# FPGA.net
KiCad netlist of a schematic drawn in Altium Designer
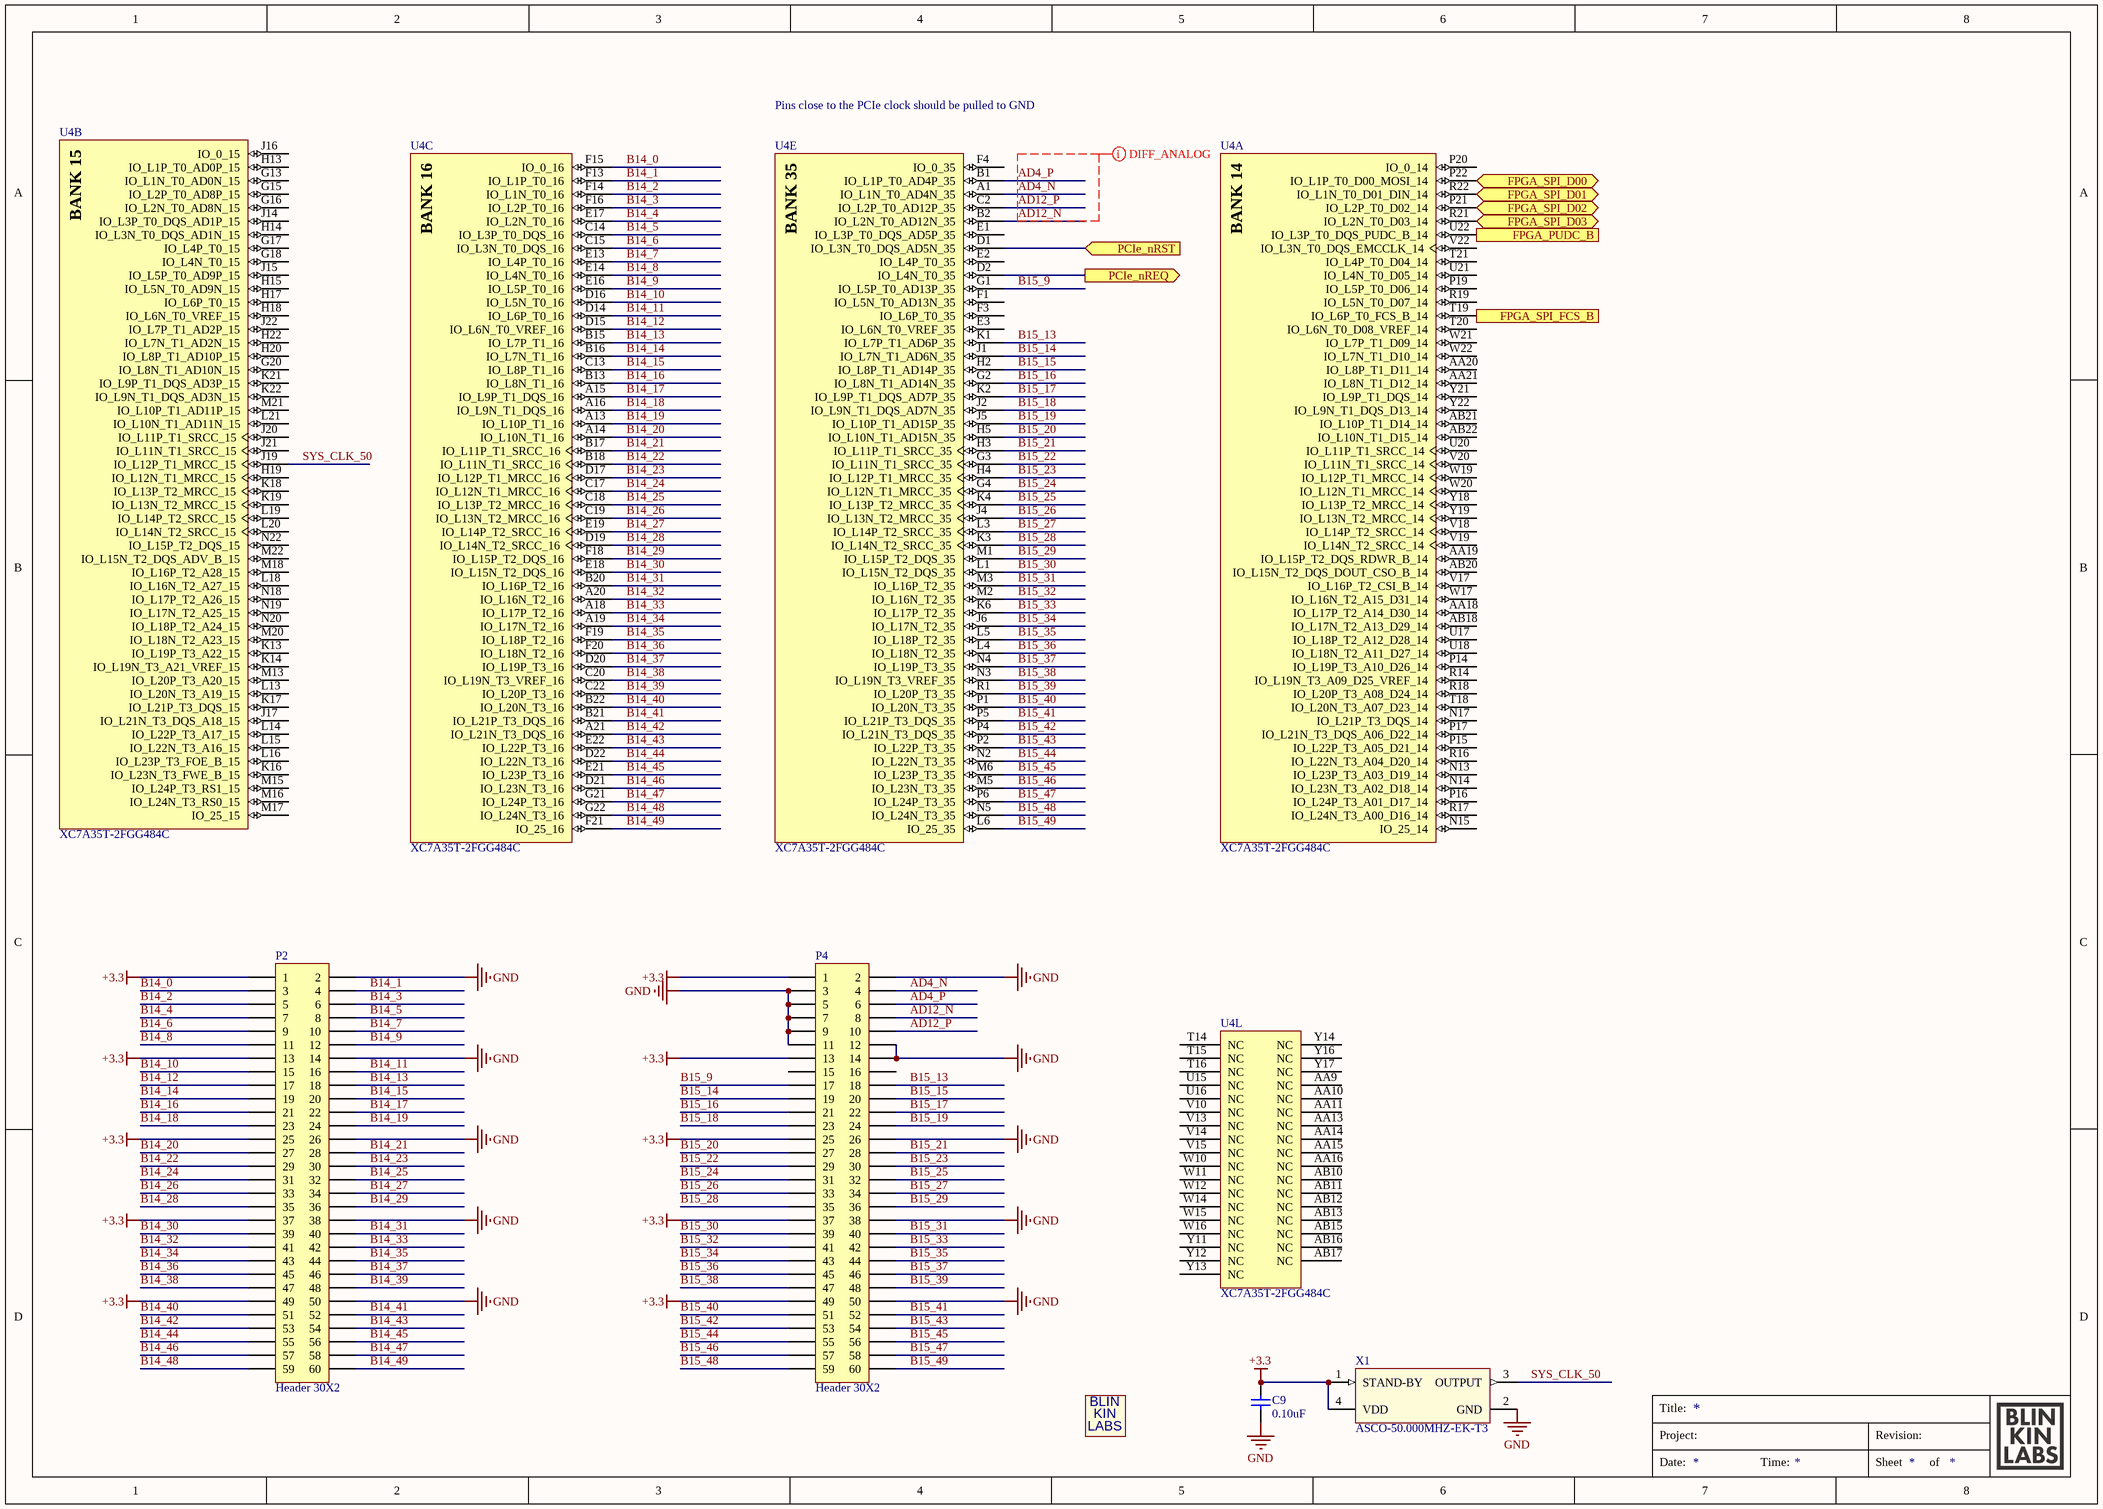
[diagram p0: FPGA.SchDoc]

(export (version "E")
  (design (tool "Eeschema 10.0.6"))
  (components
    (comp (ref "C9")
      (value "0.10uF")
      (footprint "CAPC1005X06L")
      (description "CAP CER 0.1UF 10V X5R 0402")
      (fields
        (field (name "PARTNUMBER") "GRM155R61A104KA01D")
        (field (name "DIGI-KEY PART NUMBER") "490-1318-1-ND")
      )
      (libsource (lib "cap_murata") (part "CAPACITOR"))
    )
    (comp (ref "L1")
      (value "BLINKINLABS_LOGO")
      (footprint "BLINKINLABS_LOGO")
      (description "Square logo")
      (libsource (lib "Blinkinlabs") (part "BLINKINLABS_LOGO"))
    )
    (comp (ref "P2")
      (value "Header 30X2")
      (footprint "HDR2X30")
      (description "Header, 30-Pin, Dual row")
      (fields (field (name "PUBLISHER") "Altium Limited"))
      (libsource (lib "Miscellaneous Connectors") (part "Header 30X2"))
    )
    (comp (ref "P4")
      (value "Header 30X2")
      (footprint "HDR2X30")
      (description "Header, 30-Pin, Dual row")
      (fields (field (name "PUBLISHER") "Altium Limited"))
      (libsource (lib "Miscellaneous Connectors") (part "Header 30X2"))
    )
    (comp (ref "U4")
      (value "XC7A35T-2FGG484C")
      (footprint "FGG484")
      (description "Artix-7 FPGA, 250 User I/Os, 4 GTP, 484-Ball BGA, Speed Grade 2, Commercial Grade, Pb-Free")
      (fields (field (name "MANUFACTURER") "Xilinx"))
      (libsource (lib "Altium Content Vault") (part "XLNX-XC7A35T-FGG484"))
    )
    (comp (ref "X1")
      (value "ASCO-50.000MHZ-EK-T3")
      (footprint "ABRA-ASCO-50.000MHZ-EK-T3-4_V")
      (description "Crystal Clock Oscillator, 50 MHz, -20 to 70 degC, 1.6 x 1.2 x 0.7 mm SMD")
      (fields (field (name "MANUFACTURER") "Abracon"))
      (libsource (lib "Altium Content Vault") (part "ABRA-ASCO-50_000MHZ-EK-T3-4"))
    )
  )
  (nets
    (net (code "1") (name "+3.3") (class "Default")
      (node (ref "C9") (pin "2") (pinfunction "2_2") (pintype "passive"))
      (node (ref "P2") (pin "1") (pinfunction "1_1") (pintype "passive"))
      (node (ref "P2") (pin "13") (pinfunction "13_13") (pintype "passive"))
      (node (ref "P2") (pin "25") (pinfunction "25_25") (pintype "passive"))
      (node (ref "P2") (pin "37") (pinfunction "37_37") (pintype "passive"))
      (node (ref "P2") (pin "49") (pinfunction "49_49") (pintype "passive"))
      (node (ref "P4") (pin "1") (pinfunction "1_1") (pintype "passive"))
      (node (ref "P4") (pin "13") (pinfunction "13_13") (pintype "passive"))
      (node (ref "P4") (pin "25") (pinfunction "25_25") (pintype "passive"))
      (node (ref "P4") (pin "37") (pinfunction "37_37") (pintype "passive"))
      (node (ref "P4") (pin "49") (pinfunction "49_49") (pintype "passive"))
      (node (ref "X1") (pin "1") (pinfunction "STAND-BY_1") (pintype "input"))
      (node (ref "X1") (pin "4") (pinfunction "VDD_4") (pintype "power_in"))
    )
    (net (code "2") (name "/AD4_N") (class "Default")
      (node (ref "P4") (pin "4") (pinfunction "4_4") (pintype "passive"))
      (node (ref "U4") (pin "A1") (pinfunction "IO_L1N_T0_AD4N_35_A1") (pintype "bidirectional"))
    )
    (net (code "3") (name "/AD4_P") (class "Default")
      (node (ref "P4") (pin "6") (pinfunction "6_6") (pintype "passive"))
      (node (ref "U4") (pin "B1") (pinfunction "IO_L1P_T0_AD4P_35_B1") (pintype "bidirectional"))
    )
    (net (code "4") (name "/AD12_N") (class "Default")
      (node (ref "P4") (pin "8") (pinfunction "8_8") (pintype "passive"))
      (node (ref "U4") (pin "B2") (pinfunction "IO_L2N_T0_AD12N_35_B2") (pintype "bidirectional"))
    )
    (net (code "5") (name "/AD12_P") (class "Default")
      (node (ref "P4") (pin "10") (pinfunction "10_10") (pintype "passive"))
      (node (ref "U4") (pin "C2") (pinfunction "IO_L2P_T0_AD12P_35_C2") (pintype "bidirectional"))
    )
    (net (code "6") (name "/B14_0") (class "Default")
      (node (ref "P2") (pin "3") (pinfunction "3_3") (pintype "passive"))
      (node (ref "U4") (pin "F15") (pinfunction "IO_0_16_F15") (pintype "bidirectional"))
    )
    (net (code "7") (name "/B14_1") (class "Default")
      (node (ref "P2") (pin "4") (pinfunction "4_4") (pintype "passive"))
      (node (ref "U4") (pin "F13") (pinfunction "IO_L1P_T0_16_F13") (pintype "bidirectional"))
    )
    (net (code "8") (name "/B14_2") (class "Default")
      (node (ref "P2") (pin "5") (pinfunction "5_5") (pintype "passive"))
      (node (ref "U4") (pin "F14") (pinfunction "IO_L1N_T0_16_F14") (pintype "bidirectional"))
    )
    (net (code "9") (name "/B14_3") (class "Default")
      (node (ref "P2") (pin "6") (pinfunction "6_6") (pintype "passive"))
      (node (ref "U4") (pin "F16") (pinfunction "IO_L2P_T0_16_F16") (pintype "bidirectional"))
    )
    (net (code "10") (name "/B14_4") (class "Default")
      (node (ref "P2") (pin "7") (pinfunction "7_7") (pintype "passive"))
      (node (ref "U4") (pin "E17") (pinfunction "IO_L2N_T0_16_E17") (pintype "bidirectional"))
    )
    (net (code "11") (name "/B14_5") (class "Default")
      (node (ref "P2") (pin "8") (pinfunction "8_8") (pintype "passive"))
      (node (ref "U4") (pin "C14") (pinfunction "IO_L3P_T0_DQS_16_C14") (pintype "bidirectional"))
    )
    (net (code "12") (name "/B14_6") (class "Default")
      (node (ref "P2") (pin "9") (pinfunction "9_9") (pintype "passive"))
      (node (ref "U4") (pin "C15") (pinfunction "IO_L3N_T0_DQS_16_C15") (pintype "bidirectional"))
    )
    (net (code "13") (name "/B14_7") (class "Default")
      (node (ref "P2") (pin "10") (pinfunction "10_10") (pintype "passive"))
      (node (ref "U4") (pin "E13") (pinfunction "IO_L4P_T0_16_E13") (pintype "bidirectional"))
    )
    (net (code "14") (name "/B14_8") (class "Default")
      (node (ref "P2") (pin "11") (pinfunction "11_11") (pintype "passive"))
      (node (ref "U4") (pin "E14") (pinfunction "IO_L4N_T0_16_E14") (pintype "bidirectional"))
    )
    (net (code "15") (name "/B14_9") (class "Default")
      (node (ref "P2") (pin "12") (pinfunction "12_12") (pintype "passive"))
      (node (ref "U4") (pin "E16") (pinfunction "IO_L5P_T0_16_E16") (pintype "bidirectional"))
    )
    (net (code "16") (name "/B14_10") (class "Default")
      (node (ref "P2") (pin "15") (pinfunction "15_15") (pintype "passive"))
      (node (ref "U4") (pin "D16") (pinfunction "IO_L5N_T0_16_D16") (pintype "bidirectional"))
    )
    (net (code "17") (name "/B14_11") (class "Default")
      (node (ref "P2") (pin "16") (pinfunction "16_16") (pintype "passive"))
      (node (ref "U4") (pin "D14") (pinfunction "IO_L6P_T0_16_D14") (pintype "bidirectional"))
    )
    (net (code "18") (name "/B14_12") (class "Default")
      (node (ref "P2") (pin "17") (pinfunction "17_17") (pintype "passive"))
      (node (ref "U4") (pin "D15") (pinfunction "IO_L6N_T0_VREF_16_D15") (pintype "bidirectional"))
    )
    (net (code "19") (name "/B14_13") (class "Default")
      (node (ref "P2") (pin "18") (pinfunction "18_18") (pintype "passive"))
      (node (ref "U4") (pin "B15") (pinfunction "IO_L7P_T1_16_B15") (pintype "bidirectional"))
    )
    (net (code "20") (name "/B14_14") (class "Default")
      (node (ref "P2") (pin "19") (pinfunction "19_19") (pintype "passive"))
      (node (ref "U4") (pin "B16") (pinfunction "IO_L7N_T1_16_B16") (pintype "bidirectional"))
    )
    (net (code "21") (name "/B14_15") (class "Default")
      (node (ref "P2") (pin "20") (pinfunction "20_20") (pintype "passive"))
      (node (ref "U4") (pin "C13") (pinfunction "IO_L8P_T1_16_C13") (pintype "bidirectional"))
    )
    (net (code "22") (name "/B14_16") (class "Default")
      (node (ref "P2") (pin "21") (pinfunction "21_21") (pintype "passive"))
      (node (ref "U4") (pin "B13") (pinfunction "IO_L8N_T1_16_B13") (pintype "bidirectional"))
    )
    (net (code "23") (name "/B14_17") (class "Default")
      (node (ref "P2") (pin "22") (pinfunction "22_22") (pintype "passive"))
      (node (ref "U4") (pin "A15") (pinfunction "IO_L9P_T1_DQS_16_A15") (pintype "bidirectional"))
    )
    (net (code "24") (name "/B14_18") (class "Default")
      (node (ref "P2") (pin "23") (pinfunction "23_23") (pintype "passive"))
      (node (ref "U4") (pin "A16") (pinfunction "IO_L9N_T1_DQS_16_A16") (pintype "bidirectional"))
    )
    (net (code "25") (name "/B14_19") (class "Default")
      (node (ref "P2") (pin "24") (pinfunction "24_24") (pintype "passive"))
      (node (ref "U4") (pin "A13") (pinfunction "IO_L10P_T1_16_A13") (pintype "bidirectional"))
    )
    (net (code "26") (name "/B14_20") (class "Default")
      (node (ref "P2") (pin "27") (pinfunction "27_27") (pintype "passive"))
      (node (ref "U4") (pin "A14") (pinfunction "IO_L10N_T1_16_A14") (pintype "bidirectional"))
    )
    (net (code "27") (name "/B14_21") (class "Default")
      (node (ref "P2") (pin "28") (pinfunction "28_28") (pintype "passive"))
      (node (ref "U4") (pin "B17") (pinfunction "IO_L11P_T1_SRCC_16_B17") (pintype "bidirectional"))
    )
    (net (code "28") (name "/B14_22") (class "Default")
      (node (ref "P2") (pin "29") (pinfunction "29_29") (pintype "passive"))
      (node (ref "U4") (pin "B18") (pinfunction "IO_L11N_T1_SRCC_16_B18") (pintype "bidirectional"))
    )
    (net (code "29") (name "/B14_23") (class "Default")
      (node (ref "P2") (pin "30") (pinfunction "30_30") (pintype "passive"))
      (node (ref "U4") (pin "D17") (pinfunction "IO_L12P_T1_MRCC_16_D17") (pintype "bidirectional"))
    )
    (net (code "30") (name "/B14_24") (class "Default")
      (node (ref "P2") (pin "31") (pinfunction "31_31") (pintype "passive"))
      (node (ref "U4") (pin "C17") (pinfunction "IO_L12N_T1_MRCC_16_C17") (pintype "bidirectional"))
    )
    (net (code "31") (name "/B14_25") (class "Default")
      (node (ref "P2") (pin "32") (pinfunction "32_32") (pintype "passive"))
      (node (ref "U4") (pin "C18") (pinfunction "IO_L13P_T2_MRCC_16_C18") (pintype "bidirectional"))
    )
    (net (code "32") (name "/B14_26") (class "Default")
      (node (ref "P2") (pin "33") (pinfunction "33_33") (pintype "passive"))
      (node (ref "U4") (pin "C19") (pinfunction "IO_L13N_T2_MRCC_16_C19") (pintype "bidirectional"))
    )
    (net (code "33") (name "/B14_27") (class "Default")
      (node (ref "P2") (pin "34") (pinfunction "34_34") (pintype "passive"))
      (node (ref "U4") (pin "E19") (pinfunction "IO_L14P_T2_SRCC_16_E19") (pintype "bidirectional"))
    )
    (net (code "34") (name "/B14_28") (class "Default")
      (node (ref "P2") (pin "35") (pinfunction "35_35") (pintype "passive"))
      (node (ref "U4") (pin "D19") (pinfunction "IO_L14N_T2_SRCC_16_D19") (pintype "bidirectional"))
    )
    (net (code "35") (name "/B14_29") (class "Default")
      (node (ref "P2") (pin "36") (pinfunction "36_36") (pintype "passive"))
      (node (ref "U4") (pin "F18") (pinfunction "IO_L15P_T2_DQS_16_F18") (pintype "bidirectional"))
    )
    (net (code "36") (name "/B14_30") (class "Default")
      (node (ref "P2") (pin "39") (pinfunction "39_39") (pintype "passive"))
      (node (ref "U4") (pin "E18") (pinfunction "IO_L15N_T2_DQS_16_E18") (pintype "bidirectional"))
    )
    (net (code "37") (name "/B14_31") (class "Default")
      (node (ref "P2") (pin "40") (pinfunction "40_40") (pintype "passive"))
      (node (ref "U4") (pin "B20") (pinfunction "IO_L16P_T2_16_B20") (pintype "bidirectional"))
    )
    (net (code "38") (name "/B14_32") (class "Default")
      (node (ref "P2") (pin "41") (pinfunction "41_41") (pintype "passive"))
      (node (ref "U4") (pin "A20") (pinfunction "IO_L16N_T2_16_A20") (pintype "bidirectional"))
    )
    (net (code "39") (name "/B14_33") (class "Default")
      (node (ref "P2") (pin "42") (pinfunction "42_42") (pintype "passive"))
      (node (ref "U4") (pin "A18") (pinfunction "IO_L17P_T2_16_A18") (pintype "bidirectional"))
    )
    (net (code "40") (name "/B14_34") (class "Default")
      (node (ref "P2") (pin "43") (pinfunction "43_43") (pintype "passive"))
      (node (ref "U4") (pin "A19") (pinfunction "IO_L17N_T2_16_A19") (pintype "bidirectional"))
    )
    (net (code "41") (name "/B14_35") (class "Default")
      (node (ref "P2") (pin "44") (pinfunction "44_44") (pintype "passive"))
      (node (ref "U4") (pin "F19") (pinfunction "IO_L18P_T2_16_F19") (pintype "bidirectional"))
    )
    (net (code "42") (name "/B14_36") (class "Default")
      (node (ref "P2") (pin "45") (pinfunction "45_45") (pintype "passive"))
      (node (ref "U4") (pin "F20") (pinfunction "IO_L18N_T2_16_F20") (pintype "bidirectional"))
    )
    (net (code "43") (name "/B14_37") (class "Default")
      (node (ref "P2") (pin "46") (pinfunction "46_46") (pintype "passive"))
      (node (ref "U4") (pin "D20") (pinfunction "IO_L19P_T3_16_D20") (pintype "bidirectional"))
    )
    (net (code "44") (name "/B14_38") (class "Default")
      (node (ref "P2") (pin "47") (pinfunction "47_47") (pintype "passive"))
      (node (ref "U4") (pin "C20") (pinfunction "IO_L19N_T3_VREF_16_C20") (pintype "bidirectional"))
    )
    (net (code "45") (name "/B14_39") (class "Default")
      (node (ref "P2") (pin "48") (pinfunction "48_48") (pintype "passive"))
      (node (ref "U4") (pin "C22") (pinfunction "IO_L20P_T3_16_C22") (pintype "bidirectional"))
    )
    (net (code "46") (name "/B14_40") (class "Default")
      (node (ref "P2") (pin "51") (pinfunction "51_51") (pintype "passive"))
      (node (ref "U4") (pin "B22") (pinfunction "IO_L20N_T3_16_B22") (pintype "bidirectional"))
    )
    (net (code "47") (name "/B14_41") (class "Default")
      (node (ref "P2") (pin "52") (pinfunction "52_52") (pintype "passive"))
      (node (ref "U4") (pin "B21") (pinfunction "IO_L21P_T3_DQS_16_B21") (pintype "bidirectional"))
    )
    (net (code "48") (name "/B14_42") (class "Default")
      (node (ref "P2") (pin "53") (pinfunction "53_53") (pintype "passive"))
      (node (ref "U4") (pin "A21") (pinfunction "IO_L21N_T3_DQS_16_A21") (pintype "bidirectional"))
    )
    (net (code "49") (name "/B14_43") (class "Default")
      (node (ref "P2") (pin "54") (pinfunction "54_54") (pintype "passive"))
      (node (ref "U4") (pin "E22") (pinfunction "IO_L22P_T3_16_E22") (pintype "bidirectional"))
    )
    (net (code "50") (name "/B14_44") (class "Default")
      (node (ref "P2") (pin "55") (pinfunction "55_55") (pintype "passive"))
      (node (ref "U4") (pin "D22") (pinfunction "IO_L22N_T3_16_D22") (pintype "bidirectional"))
    )
    (net (code "51") (name "/B14_45") (class "Default")
      (node (ref "P2") (pin "56") (pinfunction "56_56") (pintype "passive"))
      (node (ref "U4") (pin "E21") (pinfunction "IO_L23P_T3_16_E21") (pintype "bidirectional"))
    )
    (net (code "52") (name "/B14_46") (class "Default")
      (node (ref "P2") (pin "57") (pinfunction "57_57") (pintype "passive"))
      (node (ref "U4") (pin "D21") (pinfunction "IO_L23N_T3_16_D21") (pintype "bidirectional"))
    )
    (net (code "53") (name "/B14_47") (class "Default")
      (node (ref "P2") (pin "58") (pinfunction "58_58") (pintype "passive"))
      (node (ref "U4") (pin "G21") (pinfunction "IO_L24P_T3_16_G21") (pintype "bidirectional"))
    )
    (net (code "54") (name "/B14_48") (class "Default")
      (node (ref "P2") (pin "59") (pinfunction "59_59") (pintype "passive"))
      (node (ref "U4") (pin "G22") (pinfunction "IO_L24N_T3_16_G22") (pintype "bidirectional"))
    )
    (net (code "55") (name "/B14_49") (class "Default")
      (node (ref "P2") (pin "60") (pinfunction "60_60") (pintype "passive"))
      (node (ref "U4") (pin "F21") (pinfunction "IO_25_16_F21") (pintype "bidirectional"))
    )
    (net (code "56") (name "/B15_9") (class "Default")
      (node (ref "P4") (pin "17") (pinfunction "17_17") (pintype "passive"))
      (node (ref "U4") (pin "G1") (pinfunction "IO_L5P_T0_AD13P_35_G1") (pintype "bidirectional"))
    )
    (net (code "57") (name "/B15_13") (class "Default")
      (node (ref "P4") (pin "18") (pinfunction "18_18") (pintype "passive"))
      (node (ref "U4") (pin "K1") (pinfunction "IO_L7P_T1_AD6P_35_K1") (pintype "bidirectional"))
    )
    (net (code "58") (name "/B15_14") (class "Default")
      (node (ref "P4") (pin "19") (pinfunction "19_19") (pintype "passive"))
      (node (ref "U4") (pin "J1") (pinfunction "IO_L7N_T1_AD6N_35_J1") (pintype "bidirectional"))
    )
    (net (code "59") (name "/B15_15") (class "Default")
      (node (ref "P4") (pin "20") (pinfunction "20_20") (pintype "passive"))
      (node (ref "U4") (pin "H2") (pinfunction "IO_L8P_T1_AD14P_35_H2") (pintype "bidirectional"))
    )
    (net (code "60") (name "/B15_16") (class "Default")
      (node (ref "P4") (pin "21") (pinfunction "21_21") (pintype "passive"))
      (node (ref "U4") (pin "G2") (pinfunction "IO_L8N_T1_AD14N_35_G2") (pintype "bidirectional"))
    )
    (net (code "61") (name "/B15_17") (class "Default")
      (node (ref "P4") (pin "22") (pinfunction "22_22") (pintype "passive"))
      (node (ref "U4") (pin "K2") (pinfunction "IO_L9P_T1_DQS_AD7P_35_K2") (pintype "bidirectional"))
    )
    (net (code "62") (name "/B15_18") (class "Default")
      (node (ref "P4") (pin "23") (pinfunction "23_23") (pintype "passive"))
      (node (ref "U4") (pin "J2") (pinfunction "IO_L9N_T1_DQS_AD7N_35_J2") (pintype "bidirectional"))
    )
    (net (code "63") (name "/B15_19") (class "Default")
      (node (ref "P4") (pin "24") (pinfunction "24_24") (pintype "passive"))
      (node (ref "U4") (pin "J5") (pinfunction "IO_L10P_T1_AD15P_35_J5") (pintype "bidirectional"))
    )
    (net (code "64") (name "/B15_20") (class "Default")
      (node (ref "P4") (pin "27") (pinfunction "27_27") (pintype "passive"))
      (node (ref "U4") (pin "H5") (pinfunction "IO_L10N_T1_AD15N_35_H5") (pintype "bidirectional"))
    )
    (net (code "65") (name "/B15_21") (class "Default")
      (node (ref "P4") (pin "28") (pinfunction "28_28") (pintype "passive"))
      (node (ref "U4") (pin "H3") (pinfunction "IO_L11P_T1_SRCC_35_H3") (pintype "bidirectional"))
    )
    (net (code "66") (name "/B15_22") (class "Default")
      (node (ref "P4") (pin "29") (pinfunction "29_29") (pintype "passive"))
      (node (ref "U4") (pin "G3") (pinfunction "IO_L11N_T1_SRCC_35_G3") (pintype "bidirectional"))
    )
    (net (code "67") (name "/B15_23") (class "Default")
      (node (ref "P4") (pin "30") (pinfunction "30_30") (pintype "passive"))
      (node (ref "U4") (pin "H4") (pinfunction "IO_L12P_T1_MRCC_35_H4") (pintype "bidirectional"))
    )
    (net (code "68") (name "/B15_24") (class "Default")
      (node (ref "P4") (pin "31") (pinfunction "31_31") (pintype "passive"))
      (node (ref "U4") (pin "G4") (pinfunction "IO_L12N_T1_MRCC_35_G4") (pintype "bidirectional"))
    )
    (net (code "69") (name "/B15_25") (class "Default")
      (node (ref "P4") (pin "32") (pinfunction "32_32") (pintype "passive"))
      (node (ref "U4") (pin "K4") (pinfunction "IO_L13P_T2_MRCC_35_K4") (pintype "bidirectional"))
    )
    (net (code "70") (name "/B15_26") (class "Default")
      (node (ref "P4") (pin "33") (pinfunction "33_33") (pintype "passive"))
      (node (ref "U4") (pin "J4") (pinfunction "IO_L13N_T2_MRCC_35_J4") (pintype "bidirectional"))
    )
    (net (code "71") (name "/B15_27") (class "Default")
      (node (ref "P4") (pin "34") (pinfunction "34_34") (pintype "passive"))
      (node (ref "U4") (pin "L3") (pinfunction "IO_L14P_T2_SRCC_35_L3") (pintype "bidirectional"))
    )
    (net (code "72") (name "/B15_28") (class "Default")
      (node (ref "P4") (pin "35") (pinfunction "35_35") (pintype "passive"))
      (node (ref "U4") (pin "K3") (pinfunction "IO_L14N_T2_SRCC_35_K3") (pintype "bidirectional"))
    )
    (net (code "73") (name "/B15_29") (class "Default")
      (node (ref "P4") (pin "36") (pinfunction "36_36") (pintype "passive"))
      (node (ref "U4") (pin "M1") (pinfunction "IO_L15P_T2_DQS_35_M1") (pintype "bidirectional"))
    )
    (net (code "74") (name "/B15_30") (class "Default")
      (node (ref "P4") (pin "39") (pinfunction "39_39") (pintype "passive"))
      (node (ref "U4") (pin "L1") (pinfunction "IO_L15N_T2_DQS_35_L1") (pintype "bidirectional"))
    )
    (net (code "75") (name "/B15_31") (class "Default")
      (node (ref "P4") (pin "40") (pinfunction "40_40") (pintype "passive"))
      (node (ref "U4") (pin "M3") (pinfunction "IO_L16P_T2_35_M3") (pintype "bidirectional"))
    )
    (net (code "76") (name "/B15_32") (class "Default")
      (node (ref "P4") (pin "41") (pinfunction "41_41") (pintype "passive"))
      (node (ref "U4") (pin "M2") (pinfunction "IO_L16N_T2_35_M2") (pintype "bidirectional"))
    )
    (net (code "77") (name "/B15_33") (class "Default")
      (node (ref "P4") (pin "42") (pinfunction "42_42") (pintype "passive"))
      (node (ref "U4") (pin "K6") (pinfunction "IO_L17P_T2_35_K6") (pintype "bidirectional"))
    )
    (net (code "78") (name "/B15_34") (class "Default")
      (node (ref "P4") (pin "43") (pinfunction "43_43") (pintype "passive"))
      (node (ref "U4") (pin "J6") (pinfunction "IO_L17N_T2_35_J6") (pintype "bidirectional"))
    )
    (net (code "79") (name "/B15_35") (class "Default")
      (node (ref "P4") (pin "44") (pinfunction "44_44") (pintype "passive"))
      (node (ref "U4") (pin "L5") (pinfunction "IO_L18P_T2_35_L5") (pintype "bidirectional"))
    )
    (net (code "80") (name "/B15_36") (class "Default")
      (node (ref "P4") (pin "45") (pinfunction "45_45") (pintype "passive"))
      (node (ref "U4") (pin "L4") (pinfunction "IO_L18N_T2_35_L4") (pintype "bidirectional"))
    )
    (net (code "81") (name "/B15_37") (class "Default")
      (node (ref "P4") (pin "46") (pinfunction "46_46") (pintype "passive"))
      (node (ref "U4") (pin "N4") (pinfunction "IO_L19P_T3_35_N4") (pintype "bidirectional"))
    )
    (net (code "82") (name "/B15_38") (class "Default")
      (node (ref "P4") (pin "47") (pinfunction "47_47") (pintype "passive"))
      (node (ref "U4") (pin "N3") (pinfunction "IO_L19N_T3_VREF_35_N3") (pintype "bidirectional"))
    )
    (net (code "83") (name "/B15_39") (class "Default")
      (node (ref "P4") (pin "48") (pinfunction "48_48") (pintype "passive"))
      (node (ref "U4") (pin "R1") (pinfunction "IO_L20P_T3_35_R1") (pintype "bidirectional"))
    )
    (net (code "84") (name "/B15_40") (class "Default")
      (node (ref "P4") (pin "51") (pinfunction "51_51") (pintype "passive"))
      (node (ref "U4") (pin "P1") (pinfunction "IO_L20N_T3_35_P1") (pintype "bidirectional"))
    )
    (net (code "85") (name "/B15_41") (class "Default")
      (node (ref "P4") (pin "52") (pinfunction "52_52") (pintype "passive"))
      (node (ref "U4") (pin "P5") (pinfunction "IO_L21P_T3_DQS_35_P5") (pintype "bidirectional"))
    )
    (net (code "86") (name "/B15_42") (class "Default")
      (node (ref "P4") (pin "53") (pinfunction "53_53") (pintype "passive"))
      (node (ref "U4") (pin "P4") (pinfunction "IO_L21N_T3_DQS_35_P4") (pintype "bidirectional"))
    )
    (net (code "87") (name "/B15_43") (class "Default")
      (node (ref "P4") (pin "54") (pinfunction "54_54") (pintype "passive"))
      (node (ref "U4") (pin "P2") (pinfunction "IO_L22P_T3_35_P2") (pintype "bidirectional"))
    )
    (net (code "88") (name "/B15_44") (class "Default")
      (node (ref "P4") (pin "55") (pinfunction "55_55") (pintype "passive"))
      (node (ref "U4") (pin "N2") (pinfunction "IO_L22N_T3_35_N2") (pintype "bidirectional"))
    )
    (net (code "89") (name "/B15_45") (class "Default")
      (node (ref "P4") (pin "56") (pinfunction "56_56") (pintype "passive"))
      (node (ref "U4") (pin "M6") (pinfunction "IO_L23P_T3_35_M6") (pintype "bidirectional"))
    )
    (net (code "90") (name "/B15_46") (class "Default")
      (node (ref "P4") (pin "57") (pinfunction "57_57") (pintype "passive"))
      (node (ref "U4") (pin "M5") (pinfunction "IO_L23N_T3_35_M5") (pintype "bidirectional"))
    )
    (net (code "91") (name "/B15_47") (class "Default")
      (node (ref "P4") (pin "58") (pinfunction "58_58") (pintype "passive"))
      (node (ref "U4") (pin "P6") (pinfunction "IO_L24P_T3_35_P6") (pintype "bidirectional"))
    )
    (net (code "92") (name "/B15_48") (class "Default")
      (node (ref "P4") (pin "59") (pinfunction "59_59") (pintype "passive"))
      (node (ref "U4") (pin "N5") (pinfunction "IO_L24N_T3_35_N5") (pintype "bidirectional"))
    )
    (net (code "93") (name "/B15_49") (class "Default")
      (node (ref "P4") (pin "60") (pinfunction "60_60") (pintype "passive"))
      (node (ref "U4") (pin "L6") (pinfunction "IO_25_35_L6") (pintype "bidirectional"))
    )
    (net (code "94") (name "/FPGA_PUDC_B") (class "Default")
      (node (ref "U4") (pin "U22") (pinfunction "IO_L3P_T0_DQS_PUDC_B_14_U22") (pintype "bidirectional"))
    )
    (net (code "95") (name "/FPGA_SPI_D00") (class "Default")
      (node (ref "U4") (pin "P22") (pinfunction "IO_L1P_T0_D00_MOSI_14_P22") (pintype "bidirectional"))
    )
    (net (code "96") (name "/FPGA_SPI_D01") (class "Default")
      (node (ref "U4") (pin "R22") (pinfunction "IO_L1N_T0_D01_DIN_14_R22") (pintype "bidirectional"))
    )
    (net (code "97") (name "/FPGA_SPI_D02") (class "Default")
      (node (ref "U4") (pin "P21") (pinfunction "IO_L2P_T0_D02_14_P21") (pintype "bidirectional"))
    )
    (net (code "98") (name "/FPGA_SPI_D03") (class "Default")
      (node (ref "U4") (pin "R21") (pinfunction "IO_L2N_T0_D03_14_R21") (pintype "bidirectional"))
    )
    (net (code "99") (name "/FPGA_SPI_FCS_B") (class "Default")
      (node (ref "U4") (pin "T19") (pinfunction "IO_L6P_T0_FCS_B_14_T19") (pintype "bidirectional"))
    )
    (net (code "100") (name "/PCIe_nREQ") (class "Default")
      (node (ref "U4") (pin "D2") (pinfunction "IO_L4N_T0_35_D2") (pintype "bidirectional"))
    )
    (net (code "101") (name "/PCIe_nRST") (class "Default")
      (node (ref "U4") (pin "D1") (pinfunction "IO_L3N_T0_DQS_AD5N_35_D1") (pintype "bidirectional"))
    )
    (net (code "102") (name "/SYS_CLK_50") (class "Default")
      (node (ref "U4") (pin "J19") (pinfunction "IO_L12P_T1_MRCC_15_J19") (pintype "bidirectional"))
      (node (ref "X1") (pin "3") (pinfunction "OUTPUT_3") (pintype "output"))
    )
    (net (code "103") (name "GND") (class "Default")
      (node (ref "C9") (pin "1") (pinfunction "1_1") (pintype "passive"))
      (node (ref "P2") (pin "14") (pinfunction "14_14") (pintype "passive"))
      (node (ref "P2") (pin "2") (pinfunction "2_2") (pintype "passive"))
      (node (ref "P2") (pin "26") (pinfunction "26_26") (pintype "passive"))
      (node (ref "P2") (pin "38") (pinfunction "38_38") (pintype "passive"))
      (node (ref "P2") (pin "50") (pinfunction "50_50") (pintype "passive"))
      (node (ref "P4") (pin "11") (pinfunction "11_11") (pintype "passive"))
      (node (ref "P4") (pin "12") (pinfunction "12_12") (pintype "passive"))
      (node (ref "P4") (pin "14") (pinfunction "14_14") (pintype "passive"))
      (node (ref "P4") (pin "2") (pinfunction "2_2") (pintype "passive"))
      (node (ref "P4") (pin "26") (pinfunction "26_26") (pintype "passive"))
      (node (ref "P4") (pin "3") (pinfunction "3_3") (pintype "passive"))
      (node (ref "P4") (pin "38") (pinfunction "38_38") (pintype "passive"))
      (node (ref "P4") (pin "5") (pinfunction "5_5") (pintype "passive"))
      (node (ref "P4") (pin "50") (pinfunction "50_50") (pintype "passive"))
      (node (ref "P4") (pin "7") (pinfunction "7_7") (pintype "passive"))
      (node (ref "P4") (pin "9") (pinfunction "9_9") (pintype "passive"))
      (node (ref "X1") (pin "2") (pinfunction "GND_2") (pintype "power_in"))
    )
    (net (code "104") (name "unconnected-(P4-Pad15)") (class "Default")
      (node (ref "P4") (pin "15") (pinfunction "15_15") (pintype "passive"))
    )
    (net (code "105") (name "unconnected-(P4-Pad16)") (class "Default")
      (node (ref "P4") (pin "16") (pinfunction "16_16") (pintype "passive"))
    )
    (net (code "106") (name "unconnected-(U4A-IO_0_14-PadP20)") (class "Default")
      (node (ref "U4") (pin "P20") (pinfunction "IO_0_14_P20") (pintype "bidirectional"))
    )
    (net (code "107") (name "unconnected-(U4A-IO_25_14-PadN15)") (class "Default")
      (node (ref "U4") (pin "N15") (pinfunction "IO_25_14_N15") (pintype "bidirectional"))
    )
    (net (code "108") (name "unconnected-(U4A-IO_L3N_T0_DQS_EMCCLK_14-PadV22)") (class "Default")
      (node (ref "U4") (pin "V22") (pinfunction "IO_L3N_T0_DQS_EMCCLK_14_V22") (pintype "bidirectional"))
    )
    (net (code "109") (name "unconnected-(U4A-IO_L4N_T0_D05_14-PadU21)") (class "Default")
      (node (ref "U4") (pin "U21") (pinfunction "IO_L4N_T0_D05_14_U21") (pintype "bidirectional"))
    )
    (net (code "110") (name "unconnected-(U4A-IO_L4P_T0_D04_14-PadT21)") (class "Default")
      (node (ref "U4") (pin "T21") (pinfunction "IO_L4P_T0_D04_14_T21") (pintype "bidirectional"))
    )
    (net (code "111") (name "unconnected-(U4A-IO_L5N_T0_D07_14-PadR19)") (class "Default")
      (node (ref "U4") (pin "R19") (pinfunction "IO_L5N_T0_D07_14_R19") (pintype "bidirectional"))
    )
    (net (code "112") (name "unconnected-(U4A-IO_L5P_T0_D06_14-PadP19)") (class "Default")
      (node (ref "U4") (pin "P19") (pinfunction "IO_L5P_T0_D06_14_P19") (pintype "bidirectional"))
    )
    (net (code "113") (name "unconnected-(U4A-IO_L6N_T0_D08_VREF_14-PadT20)") (class "Default")
      (node (ref "U4") (pin "T20") (pinfunction "IO_L6N_T0_D08_VREF_14_T20") (pintype "bidirectional"))
    )
    (net (code "114") (name "unconnected-(U4A-IO_L7N_T1_D10_14-PadW22)") (class "Default")
      (node (ref "U4") (pin "W22") (pinfunction "IO_L7N_T1_D10_14_W22") (pintype "bidirectional"))
    )
    (net (code "115") (name "unconnected-(U4A-IO_L7P_T1_D09_14-PadW21)") (class "Default")
      (node (ref "U4") (pin "W21") (pinfunction "IO_L7P_T1_D09_14_W21") (pintype "bidirectional"))
    )
    (net (code "116") (name "unconnected-(U4A-IO_L8N_T1_D12_14-PadAA21)") (class "Default")
      (node (ref "U4") (pin "AA21") (pinfunction "IO_L8N_T1_D12_14_AA21") (pintype "bidirectional"))
    )
    (net (code "117") (name "unconnected-(U4A-IO_L8P_T1_D11_14-PadAA20)") (class "Default")
      (node (ref "U4") (pin "AA20") (pinfunction "IO_L8P_T1_D11_14_AA20") (pintype "bidirectional"))
    )
    (net (code "118") (name "unconnected-(U4A-IO_L9N_T1_DQS_D13_14-PadY22)") (class "Default")
      (node (ref "U4") (pin "Y22") (pinfunction "IO_L9N_T1_DQS_D13_14_Y22") (pintype "bidirectional"))
    )
    (net (code "119") (name "unconnected-(U4A-IO_L9P_T1_DQS_14-PadY21)") (class "Default")
      (node (ref "U4") (pin "Y21") (pinfunction "IO_L9P_T1_DQS_14_Y21") (pintype "bidirectional"))
    )
    (net (code "120") (name "unconnected-(U4A-IO_L10N_T1_D15_14-PadAB22)") (class "Default")
      (node (ref "U4") (pin "AB22") (pinfunction "IO_L10N_T1_D15_14_AB22") (pintype "bidirectional"))
    )
    (net (code "121") (name "unconnected-(U4A-IO_L10P_T1_D14_14-PadAB21)") (class "Default")
      (node (ref "U4") (pin "AB21") (pinfunction "IO_L10P_T1_D14_14_AB21") (pintype "bidirectional"))
    )
    (net (code "122") (name "unconnected-(U4A-IO_L11N_T1_SRCC_14-PadV20)") (class "Default")
      (node (ref "U4") (pin "V20") (pinfunction "IO_L11N_T1_SRCC_14_V20") (pintype "bidirectional"))
    )
    (net (code "123") (name "unconnected-(U4A-IO_L11P_T1_SRCC_14-PadU20)") (class "Default")
      (node (ref "U4") (pin "U20") (pinfunction "IO_L11P_T1_SRCC_14_U20") (pintype "bidirectional"))
    )
    (net (code "124") (name "unconnected-(U4A-IO_L12N_T1_MRCC_14-PadW20)") (class "Default")
      (node (ref "U4") (pin "W20") (pinfunction "IO_L12N_T1_MRCC_14_W20") (pintype "bidirectional"))
    )
    (net (code "125") (name "unconnected-(U4A-IO_L12P_T1_MRCC_14-PadW19)") (class "Default")
      (node (ref "U4") (pin "W19") (pinfunction "IO_L12P_T1_MRCC_14_W19") (pintype "bidirectional"))
    )
    (net (code "126") (name "unconnected-(U4A-IO_L13N_T2_MRCC_14-PadY19)") (class "Default")
      (node (ref "U4") (pin "Y19") (pinfunction "IO_L13N_T2_MRCC_14_Y19") (pintype "bidirectional"))
    )
    (net (code "127") (name "unconnected-(U4A-IO_L13P_T2_MRCC_14-PadY18)") (class "Default")
      (node (ref "U4") (pin "Y18") (pinfunction "IO_L13P_T2_MRCC_14_Y18") (pintype "bidirectional"))
    )
    (net (code "128") (name "unconnected-(U4A-IO_L14N_T2_SRCC_14-PadV19)") (class "Default")
      (node (ref "U4") (pin "V19") (pinfunction "IO_L14N_T2_SRCC_14_V19") (pintype "bidirectional"))
    )
    (net (code "129") (name "unconnected-(U4A-IO_L14P_T2_SRCC_14-PadV18)") (class "Default")
      (node (ref "U4") (pin "V18") (pinfunction "IO_L14P_T2_SRCC_14_V18") (pintype "bidirectional"))
    )
    (net (code "130") (name "unconnected-(U4A-IO_L15N_T2_DQS_DOUT_CSO_B_14-PadAB20)") (class "Default")
      (node (ref "U4") (pin "AB20") (pinfunction "IO_L15N_T2_DQS_DOUT_CSO_B_14_AB20") (pintype "bidirectional"))
    )
    (net (code "131") (name "unconnected-(U4A-IO_L15P_T2_DQS_RDWR_B_14-PadAA19)") (class "Default")
      (node (ref "U4") (pin "AA19") (pinfunction "IO_L15P_T2_DQS_RDWR_B_14_AA19") (pintype "bidirectional"))
    )
    (net (code "132") (name "unconnected-(U4A-IO_L16N_T2_A15_D31_14-PadW17)") (class "Default")
      (node (ref "U4") (pin "W17") (pinfunction "IO_L16N_T2_A15_D31_14_W17") (pintype "bidirectional"))
    )
    (net (code "133") (name "unconnected-(U4A-IO_L16P_T2_CSI_B_14-PadV17)") (class "Default")
      (node (ref "U4") (pin "V17") (pinfunction "IO_L16P_T2_CSI_B_14_V17") (pintype "bidirectional"))
    )
    (net (code "134") (name "unconnected-(U4A-IO_L17N_T2_A13_D29_14-PadAB18)") (class "Default")
      (node (ref "U4") (pin "AB18") (pinfunction "IO_L17N_T2_A13_D29_14_AB18") (pintype "bidirectional"))
    )
    (net (code "135") (name "unconnected-(U4A-IO_L17P_T2_A14_D30_14-PadAA18)") (class "Default")
      (node (ref "U4") (pin "AA18") (pinfunction "IO_L17P_T2_A14_D30_14_AA18") (pintype "bidirectional"))
    )
    (net (code "136") (name "unconnected-(U4A-IO_L18N_T2_A11_D27_14-PadU18)") (class "Default")
      (node (ref "U4") (pin "U18") (pinfunction "IO_L18N_T2_A11_D27_14_U18") (pintype "bidirectional"))
    )
    (net (code "137") (name "unconnected-(U4A-IO_L18P_T2_A12_D28_14-PadU17)") (class "Default")
      (node (ref "U4") (pin "U17") (pinfunction "IO_L18P_T2_A12_D28_14_U17") (pintype "bidirectional"))
    )
    (net (code "138") (name "unconnected-(U4A-IO_L19N_T3_A09_D25_VREF_14-PadR14)") (class "Default")
      (node (ref "U4") (pin "R14") (pinfunction "IO_L19N_T3_A09_D25_VREF_14_R14") (pintype "bidirectional"))
    )
    (net (code "139") (name "unconnected-(U4A-IO_L19P_T3_A10_D26_14-PadP14)") (class "Default")
      (node (ref "U4") (pin "P14") (pinfunction "IO_L19P_T3_A10_D26_14_P14") (pintype "bidirectional"))
    )
    (net (code "140") (name "unconnected-(U4A-IO_L20N_T3_A07_D23_14-PadT18)") (class "Default")
      (node (ref "U4") (pin "T18") (pinfunction "IO_L20N_T3_A07_D23_14_T18") (pintype "bidirectional"))
    )
    (net (code "141") (name "unconnected-(U4A-IO_L20P_T3_A08_D24_14-PadR18)") (class "Default")
      (node (ref "U4") (pin "R18") (pinfunction "IO_L20P_T3_A08_D24_14_R18") (pintype "bidirectional"))
    )
    (net (code "142") (name "unconnected-(U4A-IO_L21N_T3_DQS_A06_D22_14-PadP17)") (class "Default")
      (node (ref "U4") (pin "P17") (pinfunction "IO_L21N_T3_DQS_A06_D22_14_P17") (pintype "bidirectional"))
    )
    (net (code "143") (name "unconnected-(U4A-IO_L21P_T3_DQS_14-PadN17)") (class "Default")
      (node (ref "U4") (pin "N17") (pinfunction "IO_L21P_T3_DQS_14_N17") (pintype "bidirectional"))
    )
    (net (code "144") (name "unconnected-(U4A-IO_L22N_T3_A04_D20_14-PadR16)") (class "Default")
      (node (ref "U4") (pin "R16") (pinfunction "IO_L22N_T3_A04_D20_14_R16") (pintype "bidirectional"))
    )
    (net (code "145") (name "unconnected-(U4A-IO_L22P_T3_A05_D21_14-PadP15)") (class "Default")
      (node (ref "U4") (pin "P15") (pinfunction "IO_L22P_T3_A05_D21_14_P15") (pintype "bidirectional"))
    )
    (net (code "146") (name "unconnected-(U4A-IO_L23N_T3_A02_D18_14-PadN14)") (class "Default")
      (node (ref "U4") (pin "N14") (pinfunction "IO_L23N_T3_A02_D18_14_N14") (pintype "bidirectional"))
    )
    (net (code "147") (name "unconnected-(U4A-IO_L23P_T3_A03_D19_14-PadN13)") (class "Default")
      (node (ref "U4") (pin "N13") (pinfunction "IO_L23P_T3_A03_D19_14_N13") (pintype "bidirectional"))
    )
    (net (code "148") (name "unconnected-(U4A-IO_L24N_T3_A00_D16_14-PadR17)") (class "Default")
      (node (ref "U4") (pin "R17") (pinfunction "IO_L24N_T3_A00_D16_14_R17") (pintype "bidirectional"))
    )
    (net (code "149") (name "unconnected-(U4A-IO_L24P_T3_A01_D17_14-PadP16)") (class "Default")
      (node (ref "U4") (pin "P16") (pinfunction "IO_L24P_T3_A01_D17_14_P16") (pintype "bidirectional"))
    )
    (net (code "150") (name "unconnected-(U4B-IO_0_15-PadJ16)") (class "Default")
      (node (ref "U4") (pin "J16") (pinfunction "IO_0_15_J16") (pintype "bidirectional"))
    )
    (net (code "151") (name "unconnected-(U4B-IO_25_15-PadM17)") (class "Default")
      (node (ref "U4") (pin "M17") (pinfunction "IO_25_15_M17") (pintype "bidirectional"))
    )
    (net (code "152") (name "unconnected-(U4B-IO_L1N_T0_AD0N_15-PadG13)") (class "Default")
      (node (ref "U4") (pin "G13") (pinfunction "IO_L1N_T0_AD0N_15_G13") (pintype "bidirectional"))
    )
    (net (code "153") (name "unconnected-(U4B-IO_L1P_T0_AD0P_15-PadH13)") (class "Default")
      (node (ref "U4") (pin "H13") (pinfunction "IO_L1P_T0_AD0P_15_H13") (pintype "bidirectional"))
    )
    (net (code "154") (name "unconnected-(U4B-IO_L2N_T0_AD8N_15-PadG16)") (class "Default")
      (node (ref "U4") (pin "G16") (pinfunction "IO_L2N_T0_AD8N_15_G16") (pintype "bidirectional"))
    )
    (net (code "155") (name "unconnected-(U4B-IO_L2P_T0_AD8P_15-PadG15)") (class "Default")
      (node (ref "U4") (pin "G15") (pinfunction "IO_L2P_T0_AD8P_15_G15") (pintype "bidirectional"))
    )
    (net (code "156") (name "unconnected-(U4B-IO_L3N_T0_DQS_AD1N_15-PadH14)") (class "Default")
      (node (ref "U4") (pin "H14") (pinfunction "IO_L3N_T0_DQS_AD1N_15_H14") (pintype "bidirectional"))
    )
    (net (code "157") (name "unconnected-(U4B-IO_L3P_T0_DQS_AD1P_15-PadJ14)") (class "Default")
      (node (ref "U4") (pin "J14") (pinfunction "IO_L3P_T0_DQS_AD1P_15_J14") (pintype "bidirectional"))
    )
    (net (code "158") (name "unconnected-(U4B-IO_L4N_T0_15-PadG18)") (class "Default")
      (node (ref "U4") (pin "G18") (pinfunction "IO_L4N_T0_15_G18") (pintype "bidirectional"))
    )
    (net (code "159") (name "unconnected-(U4B-IO_L4P_T0_15-PadG17)") (class "Default")
      (node (ref "U4") (pin "G17") (pinfunction "IO_L4P_T0_15_G17") (pintype "bidirectional"))
    )
    (net (code "160") (name "unconnected-(U4B-IO_L5N_T0_AD9N_15-PadH15)") (class "Default")
      (node (ref "U4") (pin "H15") (pinfunction "IO_L5N_T0_AD9N_15_H15") (pintype "bidirectional"))
    )
    (net (code "161") (name "unconnected-(U4B-IO_L5P_T0_AD9P_15-PadJ15)") (class "Default")
      (node (ref "U4") (pin "J15") (pinfunction "IO_L5P_T0_AD9P_15_J15") (pintype "bidirectional"))
    )
    (net (code "162") (name "unconnected-(U4B-IO_L6N_T0_VREF_15-PadH18)") (class "Default")
      (node (ref "U4") (pin "H18") (pinfunction "IO_L6N_T0_VREF_15_H18") (pintype "bidirectional"))
    )
    (net (code "163") (name "unconnected-(U4B-IO_L6P_T0_15-PadH17)") (class "Default")
      (node (ref "U4") (pin "H17") (pinfunction "IO_L6P_T0_15_H17") (pintype "bidirectional"))
    )
    (net (code "164") (name "unconnected-(U4B-IO_L7N_T1_AD2N_15-PadH22)") (class "Default")
      (node (ref "U4") (pin "H22") (pinfunction "IO_L7N_T1_AD2N_15_H22") (pintype "bidirectional"))
    )
    (net (code "165") (name "unconnected-(U4B-IO_L7P_T1_AD2P_15-PadJ22)") (class "Default")
      (node (ref "U4") (pin "J22") (pinfunction "IO_L7P_T1_AD2P_15_J22") (pintype "bidirectional"))
    )
    (net (code "166") (name "unconnected-(U4B-IO_L8N_T1_AD10N_15-PadG20)") (class "Default")
      (node (ref "U4") (pin "G20") (pinfunction "IO_L8N_T1_AD10N_15_G20") (pintype "bidirectional"))
    )
    (net (code "167") (name "unconnected-(U4B-IO_L8P_T1_AD10P_15-PadH20)") (class "Default")
      (node (ref "U4") (pin "H20") (pinfunction "IO_L8P_T1_AD10P_15_H20") (pintype "bidirectional"))
    )
    (net (code "168") (name "unconnected-(U4B-IO_L9N_T1_DQS_AD3N_15-PadK22)") (class "Default")
      (node (ref "U4") (pin "K22") (pinfunction "IO_L9N_T1_DQS_AD3N_15_K22") (pintype "bidirectional"))
    )
    (net (code "169") (name "unconnected-(U4B-IO_L9P_T1_DQS_AD3P_15-PadK21)") (class "Default")
      (node (ref "U4") (pin "K21") (pinfunction "IO_L9P_T1_DQS_AD3P_15_K21") (pintype "bidirectional"))
    )
    (net (code "170") (name "unconnected-(U4B-IO_L10N_T1_AD11N_15-PadL21)") (class "Default")
      (node (ref "U4") (pin "L21") (pinfunction "IO_L10N_T1_AD11N_15_L21") (pintype "bidirectional"))
    )
    (net (code "171") (name "unconnected-(U4B-IO_L10P_T1_AD11P_15-PadM21)") (class "Default")
      (node (ref "U4") (pin "M21") (pinfunction "IO_L10P_T1_AD11P_15_M21") (pintype "bidirectional"))
    )
    (net (code "172") (name "unconnected-(U4B-IO_L11N_T1_SRCC_15-PadJ21)") (class "Default")
      (node (ref "U4") (pin "J21") (pinfunction "IO_L11N_T1_SRCC_15_J21") (pintype "bidirectional"))
    )
    (net (code "173") (name "unconnected-(U4B-IO_L11P_T1_SRCC_15-PadJ20)") (class "Default")
      (node (ref "U4") (pin "J20") (pinfunction "IO_L11P_T1_SRCC_15_J20") (pintype "bidirectional"))
    )
    (net (code "174") (name "unconnected-(U4B-IO_L12N_T1_MRCC_15-PadH19)") (class "Default")
      (node (ref "U4") (pin "H19") (pinfunction "IO_L12N_T1_MRCC_15_H19") (pintype "bidirectional"))
    )
    (net (code "175") (name "unconnected-(U4B-IO_L13N_T2_MRCC_15-PadK19)") (class "Default")
      (node (ref "U4") (pin "K19") (pinfunction "IO_L13N_T2_MRCC_15_K19") (pintype "bidirectional"))
    )
    (net (code "176") (name "unconnected-(U4B-IO_L13P_T2_MRCC_15-PadK18)") (class "Default")
      (node (ref "U4") (pin "K18") (pinfunction "IO_L13P_T2_MRCC_15_K18") (pintype "bidirectional"))
    )
    (net (code "177") (name "unconnected-(U4B-IO_L14N_T2_SRCC_15-PadL20)") (class "Default")
      (node (ref "U4") (pin "L20") (pinfunction "IO_L14N_T2_SRCC_15_L20") (pintype "bidirectional"))
    )
    (net (code "178") (name "unconnected-(U4B-IO_L14P_T2_SRCC_15-PadL19)") (class "Default")
      (node (ref "U4") (pin "L19") (pinfunction "IO_L14P_T2_SRCC_15_L19") (pintype "bidirectional"))
    )
    (net (code "179") (name "unconnected-(U4B-IO_L15N_T2_DQS_ADV_B_15-PadM22)") (class "Default")
      (node (ref "U4") (pin "M22") (pinfunction "IO_L15N_T2_DQS_ADV_B_15_M22") (pintype "bidirectional"))
    )
    (net (code "180") (name "unconnected-(U4B-IO_L15P_T2_DQS_15-PadN22)") (class "Default")
      (node (ref "U4") (pin "N22") (pinfunction "IO_L15P_T2_DQS_15_N22") (pintype "bidirectional"))
    )
    (net (code "181") (name "unconnected-(U4B-IO_L16N_T2_A27_15-PadL18)") (class "Default")
      (node (ref "U4") (pin "L18") (pinfunction "IO_L16N_T2_A27_15_L18") (pintype "bidirectional"))
    )
    (net (code "182") (name "unconnected-(U4B-IO_L16P_T2_A28_15-PadM18)") (class "Default")
      (node (ref "U4") (pin "M18") (pinfunction "IO_L16P_T2_A28_15_M18") (pintype "bidirectional"))
    )
    (net (code "183") (name "unconnected-(U4B-IO_L17N_T2_A25_15-PadN19)") (class "Default")
      (node (ref "U4") (pin "N19") (pinfunction "IO_L17N_T2_A25_15_N19") (pintype "bidirectional"))
    )
    (net (code "184") (name "unconnected-(U4B-IO_L17P_T2_A26_15-PadN18)") (class "Default")
      (node (ref "U4") (pin "N18") (pinfunction "IO_L17P_T2_A26_15_N18") (pintype "bidirectional"))
    )
    (net (code "185") (name "unconnected-(U4B-IO_L18N_T2_A23_15-PadM20)") (class "Default")
      (node (ref "U4") (pin "M20") (pinfunction "IO_L18N_T2_A23_15_M20") (pintype "bidirectional"))
    )
    (net (code "186") (name "unconnected-(U4B-IO_L18P_T2_A24_15-PadN20)") (class "Default")
      (node (ref "U4") (pin "N20") (pinfunction "IO_L18P_T2_A24_15_N20") (pintype "bidirectional"))
    )
    (net (code "187") (name "unconnected-(U4B-IO_L19N_T3_A21_VREF_15-PadK14)") (class "Default")
      (node (ref "U4") (pin "K14") (pinfunction "IO_L19N_T3_A21_VREF_15_K14") (pintype "bidirectional"))
    )
    (net (code "188") (name "unconnected-(U4B-IO_L19P_T3_A22_15-PadK13)") (class "Default")
      (node (ref "U4") (pin "K13") (pinfunction "IO_L19P_T3_A22_15_K13") (pintype "bidirectional"))
    )
    (net (code "189") (name "unconnected-(U4B-IO_L20N_T3_A19_15-PadL13)") (class "Default")
      (node (ref "U4") (pin "L13") (pinfunction "IO_L20N_T3_A19_15_L13") (pintype "bidirectional"))
    )
    (net (code "190") (name "unconnected-(U4B-IO_L20P_T3_A20_15-PadM13)") (class "Default")
      (node (ref "U4") (pin "M13") (pinfunction "IO_L20P_T3_A20_15_M13") (pintype "bidirectional"))
    )
    (net (code "191") (name "unconnected-(U4B-IO_L21N_T3_DQS_A18_15-PadJ17)") (class "Default")
      (node (ref "U4") (pin "J17") (pinfunction "IO_L21N_T3_DQS_A18_15_J17") (pintype "bidirectional"))
    )
    (net (code "192") (name "unconnected-(U4B-IO_L21P_T3_DQS_15-PadK17)") (class "Default")
      (node (ref "U4") (pin "K17") (pinfunction "IO_L21P_T3_DQS_15_K17") (pintype "bidirectional"))
    )
    (net (code "193") (name "unconnected-(U4B-IO_L22N_T3_A16_15-PadL15)") (class "Default")
      (node (ref "U4") (pin "L15") (pinfunction "IO_L22N_T3_A16_15_L15") (pintype "bidirectional"))
    )
    (net (code "194") (name "unconnected-(U4B-IO_L22P_T3_A17_15-PadL14)") (class "Default")
      (node (ref "U4") (pin "L14") (pinfunction "IO_L22P_T3_A17_15_L14") (pintype "bidirectional"))
    )
    (net (code "195") (name "unconnected-(U4B-IO_L23N_T3_FWE_B_15-PadK16)") (class "Default")
      (node (ref "U4") (pin "K16") (pinfunction "IO_L23N_T3_FWE_B_15_K16") (pintype "bidirectional"))
    )
    (net (code "196") (name "unconnected-(U4B-IO_L23P_T3_FOE_B_15-PadL16)") (class "Default")
      (node (ref "U4") (pin "L16") (pinfunction "IO_L23P_T3_FOE_B_15_L16") (pintype "bidirectional"))
    )
    (net (code "197") (name "unconnected-(U4B-IO_L24N_T3_RS0_15-PadM16)") (class "Default")
      (node (ref "U4") (pin "M16") (pinfunction "IO_L24N_T3_RS0_15_M16") (pintype "bidirectional"))
    )
    (net (code "198") (name "unconnected-(U4B-IO_L24P_T3_RS1_15-PadM15)") (class "Default")
      (node (ref "U4") (pin "M15") (pinfunction "IO_L24P_T3_RS1_15_M15") (pintype "bidirectional"))
    )
    (net (code "199") (name "unconnected-(U4E-IO_0_35-PadF4)") (class "Default")
      (node (ref "U4") (pin "F4") (pinfunction "IO_0_35_F4") (pintype "bidirectional"))
    )
    (net (code "200") (name "unconnected-(U4E-IO_L3P_T0_DQS_AD5P_35-PadE1)") (class "Default")
      (node (ref "U4") (pin "E1") (pinfunction "IO_L3P_T0_DQS_AD5P_35_E1") (pintype "bidirectional"))
    )
    (net (code "201") (name "unconnected-(U4E-IO_L4P_T0_35-PadE2)") (class "Default")
      (node (ref "U4") (pin "E2") (pinfunction "IO_L4P_T0_35_E2") (pintype "bidirectional"))
    )
    (net (code "202") (name "unconnected-(U4E-IO_L5N_T0_AD13N_35-PadF1)") (class "Default")
      (node (ref "U4") (pin "F1") (pinfunction "IO_L5N_T0_AD13N_35_F1") (pintype "bidirectional"))
    )
    (net (code "203") (name "unconnected-(U4E-IO_L6N_T0_VREF_35-PadE3)") (class "Default")
      (node (ref "U4") (pin "E3") (pinfunction "IO_L6N_T0_VREF_35_E3") (pintype "bidirectional"))
    )
    (net (code "204") (name "unconnected-(U4E-IO_L6P_T0_35-PadF3)") (class "Default")
      (node (ref "U4") (pin "F3") (pinfunction "IO_L6P_T0_35_F3") (pintype "bidirectional"))
    )
    (net (code "205") (name "unconnected-(U4L-NC-PadAA9)") (class "Default")
      (node (ref "U4") (pin "AA9") (pinfunction "NC_AA9") (pintype "passive"))
    )
    (net (code "206") (name "unconnected-(U4L-NC-PadAA10)") (class "Default")
      (node (ref "U4") (pin "AA10") (pinfunction "NC_AA10") (pintype "passive"))
    )
    (net (code "207") (name "unconnected-(U4L-NC-PadAA11)") (class "Default")
      (node (ref "U4") (pin "AA11") (pinfunction "NC_AA11") (pintype "passive"))
    )
    (net (code "208") (name "unconnected-(U4L-NC-PadAA13)") (class "Default")
      (node (ref "U4") (pin "AA13") (pinfunction "NC_AA13") (pintype "passive"))
    )
    (net (code "209") (name "unconnected-(U4L-NC-PadAA14)") (class "Default")
      (node (ref "U4") (pin "AA14") (pinfunction "NC_AA14") (pintype "passive"))
    )
    (net (code "210") (name "unconnected-(U4L-NC-PadAA15)") (class "Default")
      (node (ref "U4") (pin "AA15") (pinfunction "NC_AA15") (pintype "passive"))
    )
    (net (code "211") (name "unconnected-(U4L-NC-PadAA16)") (class "Default")
      (node (ref "U4") (pin "AA16") (pinfunction "NC_AA16") (pintype "passive"))
    )
    (net (code "212") (name "unconnected-(U4L-NC-PadAB10)") (class "Default")
      (node (ref "U4") (pin "AB10") (pinfunction "NC_AB10") (pintype "passive"))
    )
    (net (code "213") (name "unconnected-(U4L-NC-PadAB11)") (class "Default")
      (node (ref "U4") (pin "AB11") (pinfunction "NC_AB11") (pintype "passive"))
    )
    (net (code "214") (name "unconnected-(U4L-NC-PadAB12)") (class "Default")
      (node (ref "U4") (pin "AB12") (pinfunction "NC_AB12") (pintype "passive"))
    )
    (net (code "215") (name "unconnected-(U4L-NC-PadAB13)") (class "Default")
      (node (ref "U4") (pin "AB13") (pinfunction "NC_AB13") (pintype "passive"))
    )
    (net (code "216") (name "unconnected-(U4L-NC-PadAB15)") (class "Default")
      (node (ref "U4") (pin "AB15") (pinfunction "NC_AB15") (pintype "passive"))
    )
    (net (code "217") (name "unconnected-(U4L-NC-PadAB16)") (class "Default")
      (node (ref "U4") (pin "AB16") (pinfunction "NC_AB16") (pintype "passive"))
    )
    (net (code "218") (name "unconnected-(U4L-NC-PadAB17)") (class "Default")
      (node (ref "U4") (pin "AB17") (pinfunction "NC_AB17") (pintype "passive"))
    )
    (net (code "219") (name "unconnected-(U4L-NC-PadT14)") (class "Default")
      (node (ref "U4") (pin "T14") (pinfunction "NC_T14") (pintype "passive"))
    )
    (net (code "220") (name "unconnected-(U4L-NC-PadT15)") (class "Default")
      (node (ref "U4") (pin "T15") (pinfunction "NC_T15") (pintype "passive"))
    )
    (net (code "221") (name "unconnected-(U4L-NC-PadT16)") (class "Default")
      (node (ref "U4") (pin "T16") (pinfunction "NC_T16") (pintype "passive"))
    )
    (net (code "222") (name "unconnected-(U4L-NC-PadU15)") (class "Default")
      (node (ref "U4") (pin "U15") (pinfunction "NC_U15") (pintype "passive"))
    )
    (net (code "223") (name "unconnected-(U4L-NC-PadU16)") (class "Default")
      (node (ref "U4") (pin "U16") (pinfunction "NC_U16") (pintype "passive"))
    )
    (net (code "224") (name "unconnected-(U4L-NC-PadV10)") (class "Default")
      (node (ref "U4") (pin "V10") (pinfunction "NC_V10") (pintype "passive"))
    )
    (net (code "225") (name "unconnected-(U4L-NC-PadV13)") (class "Default")
      (node (ref "U4") (pin "V13") (pinfunction "NC_V13") (pintype "passive"))
    )
    (net (code "226") (name "unconnected-(U4L-NC-PadV14)") (class "Default")
      (node (ref "U4") (pin "V14") (pinfunction "NC_V14") (pintype "passive"))
    )
    (net (code "227") (name "unconnected-(U4L-NC-PadV15)") (class "Default")
      (node (ref "U4") (pin "V15") (pinfunction "NC_V15") (pintype "passive"))
    )
    (net (code "228") (name "unconnected-(U4L-NC-PadW10)") (class "Default")
      (node (ref "U4") (pin "W10") (pinfunction "NC_W10") (pintype "passive"))
    )
    (net (code "229") (name "unconnected-(U4L-NC-PadW11)") (class "Default")
      (node (ref "U4") (pin "W11") (pinfunction "NC_W11") (pintype "passive"))
    )
    (net (code "230") (name "unconnected-(U4L-NC-PadW12)") (class "Default")
      (node (ref "U4") (pin "W12") (pinfunction "NC_W12") (pintype "passive"))
    )
    (net (code "231") (name "unconnected-(U4L-NC-PadW14)") (class "Default")
      (node (ref "U4") (pin "W14") (pinfunction "NC_W14") (pintype "passive"))
    )
    (net (code "232") (name "unconnected-(U4L-NC-PadW15)") (class "Default")
      (node (ref "U4") (pin "W15") (pinfunction "NC_W15") (pintype "passive"))
    )
    (net (code "233") (name "unconnected-(U4L-NC-PadW16)") (class "Default")
      (node (ref "U4") (pin "W16") (pinfunction "NC_W16") (pintype "passive"))
    )
    (net (code "234") (name "unconnected-(U4L-NC-PadY11)") (class "Default")
      (node (ref "U4") (pin "Y11") (pinfunction "NC_Y11") (pintype "passive"))
    )
    (net (code "235") (name "unconnected-(U4L-NC-PadY12)") (class "Default")
      (node (ref "U4") (pin "Y12") (pinfunction "NC_Y12") (pintype "passive"))
    )
    (net (code "236") (name "unconnected-(U4L-NC-PadY13)") (class "Default")
      (node (ref "U4") (pin "Y13") (pinfunction "NC_Y13") (pintype "passive"))
    )
    (net (code "237") (name "unconnected-(U4L-NC-PadY14)") (class "Default")
      (node (ref "U4") (pin "Y14") (pinfunction "NC_Y14") (pintype "passive"))
    )
    (net (code "238") (name "unconnected-(U4L-NC-PadY16)") (class "Default")
      (node (ref "U4") (pin "Y16") (pinfunction "NC_Y16") (pintype "passive"))
    )
    (net (code "239") (name "unconnected-(U4L-NC-PadY17)") (class "Default")
      (node (ref "U4") (pin "Y17") (pinfunction "NC_Y17") (pintype "passive"))
    )
  )
)
